# Grove-Encoder_v0_9b.net
KiCad netlist of a schematic drawn in EAGLE
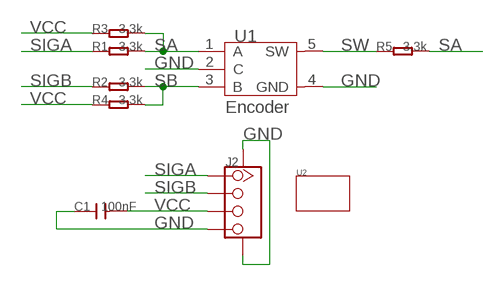
[diagram p0: schematic, sheet 1]

(export (version "E")
  (design (tool "Eeschema 10.0.6"))
  (components
    (comp (ref "C1")
      (value "100nF")
      (footprint "eagle-import:C0603")
      (libsource (lib "eagle-import") (part "C-0603"))
    )
    (comp (ref "J2")
      (value "TWIG-4P-2.0-SMD-FEMALE-REINFORCE'DD'")
      (footprint "eagle-import:4P-SMD-2.0")
      (libsource (lib "eagle-import") (part "TWIG-4P-2.0-SMD-FEMALE-REINFORCE'DD'"))
    )
    (comp (ref "R1")
      (value "3.3k")
      (footprint "eagle-import:R0603")
      (libsource (lib "eagle-import") (part "R-0603"))
    )
    (comp (ref "R2")
      (value "3.3k")
      (footprint "eagle-import:R0603")
      (libsource (lib "eagle-import") (part "R-0603"))
    )
    (comp (ref "R3")
      (value "3.3k")
      (footprint "eagle-import:R0603")
      (libsource (lib "eagle-import") (part "R-0603"))
    )
    (comp (ref "R4")
      (value "3.3k")
      (footprint "eagle-import:R0603")
      (libsource (lib "eagle-import") (part "R-0603"))
    )
    (comp (ref "R5")
      (value "3.3k")
      (footprint "eagle-import:R0603")
      (libsource (lib "eagle-import") (part "R-0603"))
    )
    (comp (ref "U1")
      (value "Encoder")
      (footprint "eagle-import:5P-13.75X11.7X6.5H")
      (libsource (lib "eagle-import") (part "ROTARY-ENCODE-5P"))
    )
    (comp (ref "U2")
      (value "TWIG'1U'")
      (footprint "eagle-import:1U-DIM-W_-DRILL")
      (libsource (lib "eagle-import") (part "TWIG'1U'"))
    )
  )
  (nets
    (net (code "1") (name "/GND") (class "Default")
      (node (ref "C1") (pin "1") (pinfunction "1_1") (pintype "passive"))
      (node (ref "J2") (pin "4") (pinfunction "4_4") (pintype "bidirectional"))
      (node (ref "J2") (pin "SS1") (pinfunction "SS1_SS1") (pintype "bidirectional"))
      (node (ref "J2") (pin "SS2") (pinfunction "SS2_SS2") (pintype "bidirectional"))
      (node (ref "U1") (pin "2") (pinfunction "C_2") (pintype "bidirectional"))
      (node (ref "U1") (pin "4") (pinfunction "GND_4") (pintype "bidirectional"))
    )
    (net (code "2") (name "/SA") (class "Default")
      (node (ref "R1") (pin "2") (pinfunction "2_2") (pintype "passive"))
      (node (ref "R3") (pin "2") (pinfunction "2_2") (pintype "passive"))
      (node (ref "R5") (pin "2") (pinfunction "2_2") (pintype "passive"))
      (node (ref "U1") (pin "1") (pinfunction "A_1") (pintype "bidirectional"))
    )
    (net (code "3") (name "/SB") (class "Default")
      (node (ref "R2") (pin "2") (pinfunction "2_2") (pintype "passive"))
      (node (ref "R4") (pin "2") (pinfunction "2_2") (pintype "passive"))
      (node (ref "U1") (pin "3") (pinfunction "B_3") (pintype "bidirectional"))
    )
    (net (code "4") (name "/SIGA") (class "Default")
      (node (ref "J2") (pin "1") (pinfunction "1_1") (pintype "bidirectional"))
      (node (ref "R1") (pin "1") (pinfunction "1_1") (pintype "passive"))
    )
    (net (code "5") (name "/SIGB") (class "Default")
      (node (ref "J2") (pin "2") (pinfunction "2_2") (pintype "bidirectional"))
      (node (ref "R2") (pin "1") (pinfunction "1_1") (pintype "passive"))
    )
    (net (code "6") (name "/SW") (class "Default")
      (node (ref "R5") (pin "1") (pinfunction "1_1") (pintype "passive"))
      (node (ref "U1") (pin "5") (pinfunction "SW_5") (pintype "bidirectional"))
    )
    (net (code "7") (name "/VCC") (class "Default")
      (node (ref "C1") (pin "2") (pinfunction "2_2") (pintype "passive"))
      (node (ref "J2") (pin "3") (pinfunction "3_3") (pintype "bidirectional"))
      (node (ref "R3") (pin "1") (pinfunction "1_1") (pintype "passive"))
      (node (ref "R4") (pin "1") (pinfunction "1_1") (pintype "passive"))
    )
  )
)
